# LEDAnzeige_Multiplexing.net
KiCad netlist of a schematic drawn in EAGLE
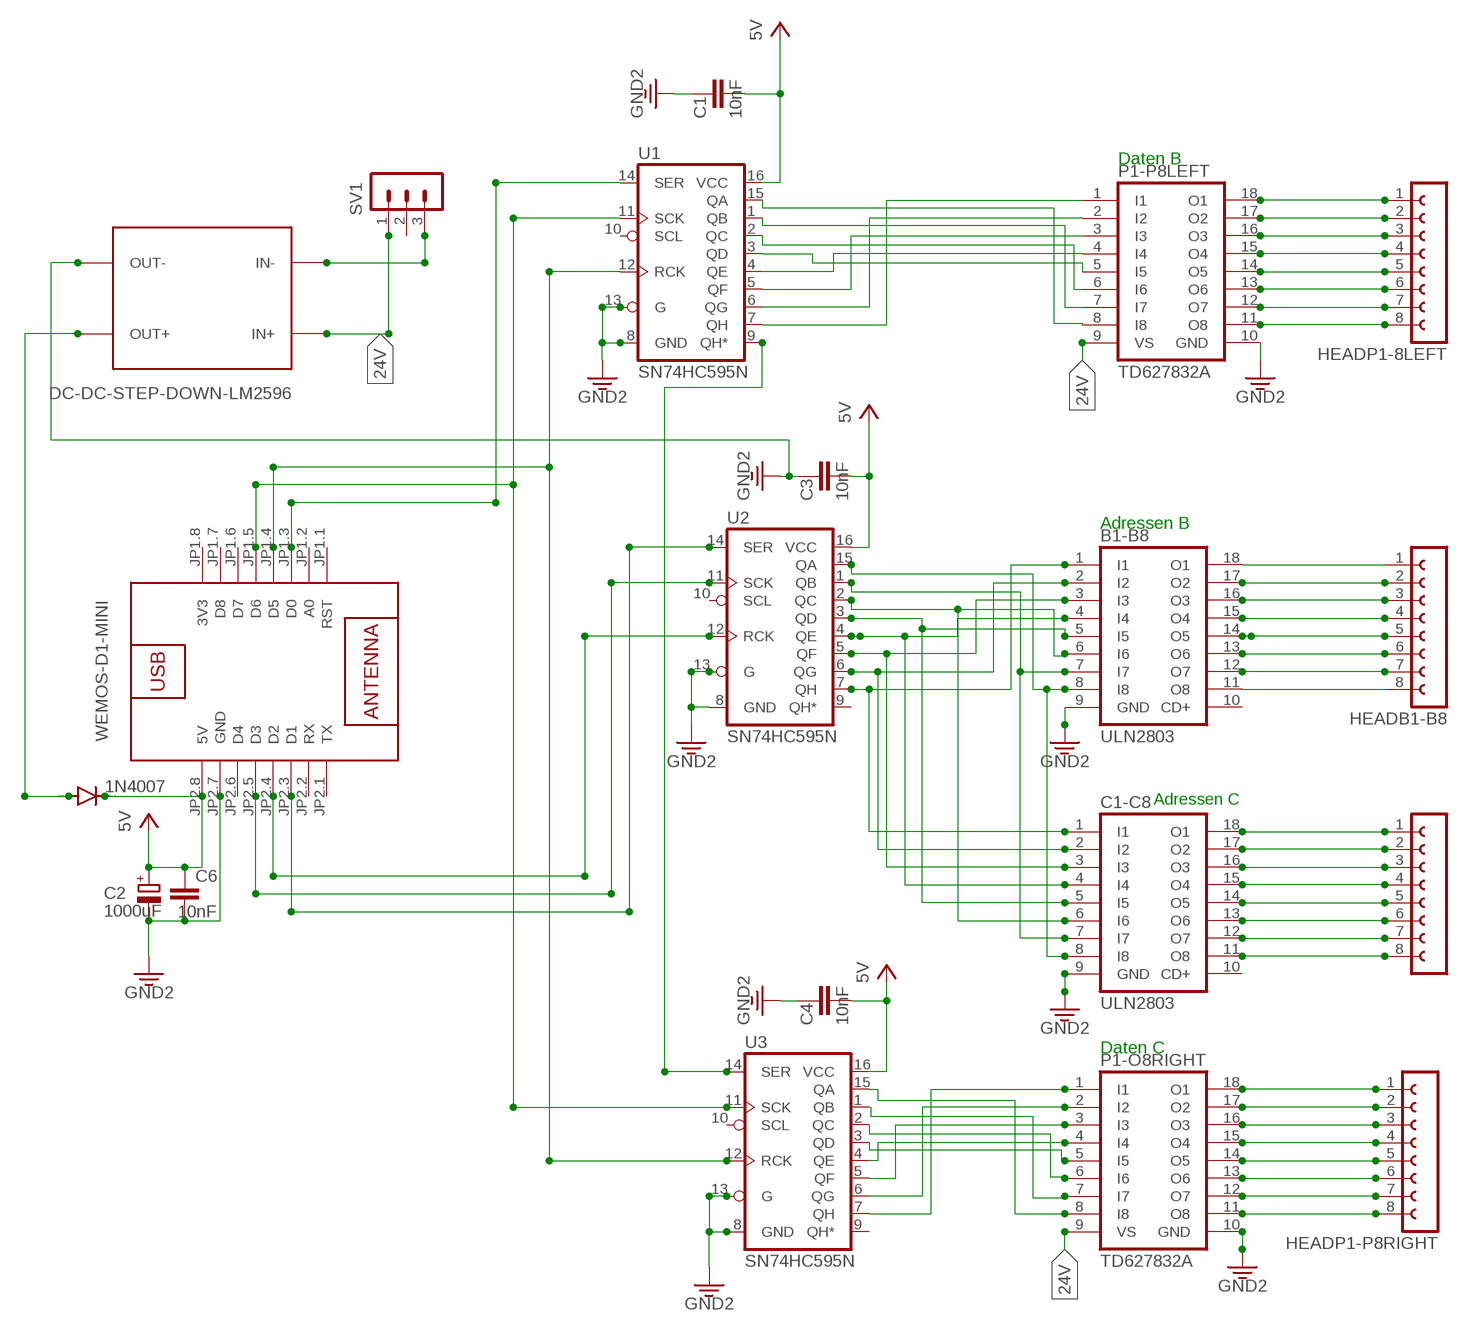
[diagram p0: schematic, sheet 1]

(export (version "E")
  (design (tool "Eeschema 10.0.6"))
  (components
    (comp (ref "1N4007")
      (value "DIODE-D-2.5")
      (footprint "eagle-import:D-2.5")
      (libsource (lib "eagle-import") (part "DIODE-D-2.5"))
    )
    (comp (ref "B1-B8")
      (value "ULN2803")
      (footprint "eagle-import:DIL18")
      (libsource (lib "eagle-import") (part "ULN2803A"))
    )
    (comp (ref "C1")
      (value "10nF")
      (footprint "eagle-import:C025-025X050")
      (libsource (lib "eagle-import") (part "C-EU025-025X050"))
    )
    (comp (ref "C1-C8")
      (value "ULN2803")
      (footprint "eagle-import:DIL18")
      (libsource (lib "eagle-import") (part "ULN2803A"))
    )
    (comp (ref "C2")
      (value "1000uF")
      (footprint "eagle-import:E5-10,5")
      (libsource (lib "eagle-import") (part "CPOL-EUE5-10.5"))
    )
    (comp (ref "C3")
      (value "10nF")
      (footprint "eagle-import:C025-025X050")
      (libsource (lib "eagle-import") (part "C-EU025-025X050"))
    )
    (comp (ref "C4")
      (value "10nF")
      (footprint "eagle-import:C025-025X050")
      (libsource (lib "eagle-import") (part "C-EU025-025X050"))
    )
    (comp (ref "C6")
      (value "10nF")
      (footprint "eagle-import:C025-025X050")
      (libsource (lib "eagle-import") (part "C-EU025-025X050"))
    )
    (comp (ref "HEADB1-B8")
      (value "FE08-1")
      (footprint "eagle-import:FE08")
      (libsource (lib "eagle-import") (part "FE08-1"))
    )
    (comp (ref "HEADC1-C8")
      (value "FE08-1")
      (footprint "eagle-import:FE08")
      (libsource (lib "eagle-import") (part "FE08-1"))
    )
    (comp (ref "HEADP1-8LEFT")
      (value "FE08-1")
      (footprint "eagle-import:FE08")
      (libsource (lib "eagle-import") (part "FE08-1"))
    )
    (comp (ref "HEADP1-P8RIGHT")
      (value "FE08-1")
      (footprint "eagle-import:FE08")
      (libsource (lib "eagle-import") (part "FE08-1"))
    )
    (comp (ref "P1-O8RIGHT")
      (value "TD627832A")
      (footprint "eagle-import:DIL18")
      (libsource (lib "eagle-import") (part "TD62783A2"))
    )
    (comp (ref "P1-P8LEFT")
      (value "TD627832A")
      (footprint "eagle-import:DIL18")
      (libsource (lib "eagle-import") (part "TD62783A2"))
    )
    (comp (ref "SV1")
      (value "MA03-1")
      (footprint "eagle-import:MA03-1")
      (libsource (lib "eagle-import") (part "MA03-1"))
    )
    (comp (ref "U$1")
      (value "WEMOS-D1-MINI")
      (footprint "eagle-import:WEMOS-D1-MINI")
      (libsource (lib "eagle-import") (part "WEMOS-D1-MINI"))
    )
    (comp (ref "U$2")
      (value "DC-DC-STEP-DOWN-LM2596")
      (footprint "eagle-import:DC-DC-STEP-DOWN-LM2596")
      (libsource (lib "eagle-import") (part "DC-DC-STEP-DOWN-LM2596"))
    )
    (comp (ref "U1")
      (value "SN74HC595N")
      (footprint "eagle-import:DIP16")
      (libsource (lib "eagle-import") (part "74595NHC"))
    )
    (comp (ref "U2")
      (value "SN74HC595N")
      (footprint "eagle-import:DIP16")
      (libsource (lib "eagle-import") (part "74595NHC"))
    )
    (comp (ref "U3")
      (value "SN74HC595N")
      (footprint "eagle-import:DIP16")
      (libsource (lib "eagle-import") (part "74595NHC"))
    )
  )
  (nets
    (net (code "1") (name "/3V3") (class "Default")
      (node (ref "U$1") (pin "JP1.8") (pinfunction "3V3_JP1.8") (pintype "power_in"))
    )
    (net (code "2") (name "5V") (class "Default")
      (node (ref "1N4007") (pin "C") (pinfunction "C_C") (pintype "passive"))
      (node (ref "C1") (pin "2") (pinfunction "2_2") (pintype "passive"))
      (node (ref "C2") (pin "+") (pinfunction "+_+") (pintype "passive"))
      (node (ref "C3") (pin "2") (pinfunction "2_2") (pintype "passive"))
      (node (ref "C4") (pin "2") (pinfunction "2_2") (pintype "passive"))
      (node (ref "C6") (pin "1") (pinfunction "1_1") (pintype "passive"))
      (node (ref "U$1") (pin "JP2.8") (pinfunction "5V_JP2.8") (pintype "power_in"))
      (node (ref "U1") (pin "16") (pinfunction "VCC_16") (pintype "power_in"))
      (node (ref "U2") (pin "16") (pinfunction "VCC_16") (pintype "power_in"))
      (node (ref "U3") (pin "16") (pinfunction "VCC_16") (pintype "power_in"))
    )
    (net (code "3") (name "24V") (class "Default")
      (node (ref "P1-O8RIGHT") (pin "9") (pinfunction "VS_9") (pintype "passive"))
      (node (ref "P1-P8LEFT") (pin "9") (pinfunction "VS_9") (pintype "passive"))
      (node (ref "SV1") (pin "1") (pinfunction "1_1") (pintype "passive"))
      (node (ref "U$2") (pin "IN+") (pinfunction "IN+_IN+") (pintype "bidirectional"))
    )
    (net (code "4") (name "GND2") (class "Default")
      (node (ref "B1-B8") (pin "9") (pinfunction "GND_9") (pintype "power_in"))
      (node (ref "C1") (pin "1") (pinfunction "1_1") (pintype "passive"))
      (node (ref "C1-C8") (pin "9") (pinfunction "GND_9") (pintype "power_in"))
      (node (ref "C2") (pin "-") (pinfunction "-_-") (pintype "passive"))
      (node (ref "C3") (pin "1") (pinfunction "1_1") (pintype "passive"))
      (node (ref "C4") (pin "1") (pinfunction "1_1") (pintype "passive"))
      (node (ref "C6") (pin "2") (pinfunction "2_2") (pintype "passive"))
      (node (ref "P1-O8RIGHT") (pin "10") (pinfunction "GND_10") (pintype "power_in"))
      (node (ref "P1-P8LEFT") (pin "10") (pinfunction "GND_10") (pintype "power_in"))
      (node (ref "U$1") (pin "JP2.7") (pinfunction "GND_JP2.7") (pintype "power_in"))
      (node (ref "U$2") (pin "OUT-") (pinfunction "OUT-_OUT-") (pintype "bidirectional"))
      (node (ref "U1") (pin "13") (pinfunction "G_13") (pintype "input"))
      (node (ref "U1") (pin "8") (pinfunction "GND_8") (pintype "power_in"))
      (node (ref "U2") (pin "13") (pinfunction "G_13") (pintype "input"))
      (node (ref "U2") (pin "8") (pinfunction "GND_8") (pintype "power_in"))
      (node (ref "U3") (pin "13") (pinfunction "G_13") (pintype "input"))
      (node (ref "U3") (pin "8") (pinfunction "GND_8") (pintype "power_in"))
    )
    (net (code "5") (name "Net-(1N4007-PadA)") (class "Default")
      (node (ref "1N4007") (pin "A") (pinfunction "A_A") (pintype "passive"))
      (node (ref "U$2") (pin "OUT+") (pinfunction "OUT+_OUT+") (pintype "bidirectional"))
    )
    (net (code "6") (name "Net-(B1-B8-I1)") (class "Default")
      (node (ref "B1-B8") (pin "1") (pinfunction "I1_1") (pintype "input"))
      (node (ref "C1-C8") (pin "1") (pinfunction "I1_1") (pintype "input"))
      (node (ref "U2") (pin "7") (pinfunction "QH_7") (pintype "tri_state"))
    )
    (net (code "7") (name "Net-(B1-B8-I2)") (class "Default")
      (node (ref "B1-B8") (pin "2") (pinfunction "I2_2") (pintype "input"))
      (node (ref "C1-C8") (pin "2") (pinfunction "I2_2") (pintype "input"))
      (node (ref "U2") (pin "6") (pinfunction "QG_6") (pintype "tri_state"))
    )
    (net (code "8") (name "Net-(B1-B8-I3)") (class "Default")
      (node (ref "B1-B8") (pin "3") (pinfunction "I3_3") (pintype "input"))
      (node (ref "C1-C8") (pin "3") (pinfunction "I3_3") (pintype "input"))
      (node (ref "U2") (pin "5") (pinfunction "QF_5") (pintype "tri_state"))
    )
    (net (code "9") (name "Net-(B1-B8-I4)") (class "Default")
      (node (ref "B1-B8") (pin "4") (pinfunction "I4_4") (pintype "input"))
      (node (ref "C1-C8") (pin "4") (pinfunction "I4_4") (pintype "input"))
      (node (ref "U2") (pin "4") (pinfunction "QE_4") (pintype "tri_state"))
    )
    (net (code "10") (name "Net-(B1-B8-I5)") (class "Default")
      (node (ref "B1-B8") (pin "5") (pinfunction "I5_5") (pintype "input"))
      (node (ref "C1-C8") (pin "5") (pinfunction "I5_5") (pintype "input"))
      (node (ref "U2") (pin "3") (pinfunction "QD_3") (pintype "tri_state"))
    )
    (net (code "11") (name "Net-(B1-B8-I6)") (class "Default")
      (node (ref "B1-B8") (pin "6") (pinfunction "I6_6") (pintype "input"))
      (node (ref "C1-C8") (pin "6") (pinfunction "I6_6") (pintype "input"))
      (node (ref "U2") (pin "2") (pinfunction "QC_2") (pintype "tri_state"))
    )
    (net (code "12") (name "Net-(B1-B8-I7)") (class "Default")
      (node (ref "B1-B8") (pin "7") (pinfunction "I7_7") (pintype "input"))
      (node (ref "C1-C8") (pin "7") (pinfunction "I7_7") (pintype "input"))
      (node (ref "U2") (pin "1") (pinfunction "QB_1") (pintype "tri_state"))
    )
    (net (code "13") (name "Net-(B1-B8-I8)") (class "Default")
      (node (ref "B1-B8") (pin "8") (pinfunction "I8_8") (pintype "input"))
      (node (ref "C1-C8") (pin "8") (pinfunction "I8_8") (pintype "input"))
      (node (ref "U2") (pin "15") (pinfunction "QA_15") (pintype "tri_state"))
    )
    (net (code "14") (name "Net-(B1-B8-O1)") (class "Default")
      (node (ref "B1-B8") (pin "18") (pinfunction "O1_18") (pintype "open_collector"))
      (node (ref "HEADB1-B8") (pin "1") (pinfunction "1_1") (pintype "passive"))
    )
    (net (code "15") (name "Net-(B1-B8-O2)") (class "Default")
      (node (ref "B1-B8") (pin "17") (pinfunction "O2_17") (pintype "open_collector"))
      (node (ref "HEADB1-B8") (pin "2") (pinfunction "2_2") (pintype "passive"))
    )
    (net (code "16") (name "Net-(B1-B8-O3)") (class "Default")
      (node (ref "B1-B8") (pin "16") (pinfunction "O3_16") (pintype "open_collector"))
      (node (ref "HEADB1-B8") (pin "3") (pinfunction "3_3") (pintype "passive"))
    )
    (net (code "17") (name "Net-(B1-B8-O4)") (class "Default")
      (node (ref "B1-B8") (pin "15") (pinfunction "O4_15") (pintype "open_collector"))
      (node (ref "HEADB1-B8") (pin "4") (pinfunction "4_4") (pintype "passive"))
    )
    (net (code "18") (name "Net-(B1-B8-O5)") (class "Default")
      (node (ref "B1-B8") (pin "14") (pinfunction "O5_14") (pintype "open_collector"))
      (node (ref "HEADB1-B8") (pin "5") (pinfunction "5_5") (pintype "passive"))
    )
    (net (code "19") (name "Net-(B1-B8-O6)") (class "Default")
      (node (ref "B1-B8") (pin "13") (pinfunction "O6_13") (pintype "open_collector"))
      (node (ref "HEADB1-B8") (pin "6") (pinfunction "6_6") (pintype "passive"))
    )
    (net (code "20") (name "Net-(B1-B8-O7)") (class "Default")
      (node (ref "B1-B8") (pin "12") (pinfunction "O7_12") (pintype "open_collector"))
      (node (ref "HEADB1-B8") (pin "7") (pinfunction "7_7") (pintype "passive"))
    )
    (net (code "21") (name "Net-(B1-B8-O8)") (class "Default")
      (node (ref "B1-B8") (pin "11") (pinfunction "O8_11") (pintype "open_collector"))
      (node (ref "HEADB1-B8") (pin "8") (pinfunction "8_8") (pintype "passive"))
    )
    (net (code "22") (name "Net-(C1-C8-O1)") (class "Default")
      (node (ref "C1-C8") (pin "18") (pinfunction "O1_18") (pintype "open_collector"))
      (node (ref "HEADC1-C8") (pin "1") (pinfunction "1_1") (pintype "passive"))
    )
    (net (code "23") (name "Net-(C1-C8-O2)") (class "Default")
      (node (ref "C1-C8") (pin "17") (pinfunction "O2_17") (pintype "open_collector"))
      (node (ref "HEADC1-C8") (pin "2") (pinfunction "2_2") (pintype "passive"))
    )
    (net (code "24") (name "Net-(C1-C8-O3)") (class "Default")
      (node (ref "C1-C8") (pin "16") (pinfunction "O3_16") (pintype "open_collector"))
      (node (ref "HEADC1-C8") (pin "3") (pinfunction "3_3") (pintype "passive"))
    )
    (net (code "25") (name "Net-(C1-C8-O4)") (class "Default")
      (node (ref "C1-C8") (pin "15") (pinfunction "O4_15") (pintype "open_collector"))
      (node (ref "HEADC1-C8") (pin "4") (pinfunction "4_4") (pintype "passive"))
    )
    (net (code "26") (name "Net-(C1-C8-O5)") (class "Default")
      (node (ref "C1-C8") (pin "14") (pinfunction "O5_14") (pintype "open_collector"))
      (node (ref "HEADC1-C8") (pin "5") (pinfunction "5_5") (pintype "passive"))
    )
    (net (code "27") (name "Net-(C1-C8-O6)") (class "Default")
      (node (ref "C1-C8") (pin "13") (pinfunction "O6_13") (pintype "open_collector"))
      (node (ref "HEADC1-C8") (pin "6") (pinfunction "6_6") (pintype "passive"))
    )
    (net (code "28") (name "Net-(C1-C8-O7)") (class "Default")
      (node (ref "C1-C8") (pin "12") (pinfunction "O7_12") (pintype "open_collector"))
      (node (ref "HEADC1-C8") (pin "7") (pinfunction "7_7") (pintype "passive"))
    )
    (net (code "29") (name "Net-(C1-C8-O8)") (class "Default")
      (node (ref "C1-C8") (pin "11") (pinfunction "O8_11") (pintype "open_collector"))
      (node (ref "HEADC1-C8") (pin "8") (pinfunction "8_8") (pintype "passive"))
    )
    (net (code "30") (name "Net-(P1-O8RIGHT-I1)") (class "Default")
      (node (ref "P1-O8RIGHT") (pin "1") (pinfunction "I1_1") (pintype "input"))
      (node (ref "U3") (pin "7") (pinfunction "QH_7") (pintype "tri_state"))
    )
    (net (code "31") (name "Net-(P1-O8RIGHT-I2)") (class "Default")
      (node (ref "P1-O8RIGHT") (pin "2") (pinfunction "I2_2") (pintype "input"))
      (node (ref "U3") (pin "6") (pinfunction "QG_6") (pintype "tri_state"))
    )
    (net (code "32") (name "Net-(P1-O8RIGHT-I3)") (class "Default")
      (node (ref "P1-O8RIGHT") (pin "3") (pinfunction "I3_3") (pintype "input"))
      (node (ref "U3") (pin "5") (pinfunction "QF_5") (pintype "tri_state"))
    )
    (net (code "33") (name "Net-(P1-O8RIGHT-I4)") (class "Default")
      (node (ref "P1-O8RIGHT") (pin "4") (pinfunction "I4_4") (pintype "input"))
      (node (ref "U3") (pin "4") (pinfunction "QE_4") (pintype "tri_state"))
    )
    (net (code "34") (name "Net-(P1-O8RIGHT-I5)") (class "Default")
      (node (ref "P1-O8RIGHT") (pin "5") (pinfunction "I5_5") (pintype "input"))
      (node (ref "U3") (pin "3") (pinfunction "QD_3") (pintype "tri_state"))
    )
    (net (code "35") (name "Net-(P1-O8RIGHT-I6)") (class "Default")
      (node (ref "P1-O8RIGHT") (pin "6") (pinfunction "I6_6") (pintype "input"))
      (node (ref "U3") (pin "2") (pinfunction "QC_2") (pintype "tri_state"))
    )
    (net (code "36") (name "Net-(P1-O8RIGHT-I7)") (class "Default")
      (node (ref "P1-O8RIGHT") (pin "7") (pinfunction "I7_7") (pintype "input"))
      (node (ref "U3") (pin "1") (pinfunction "QB_1") (pintype "tri_state"))
    )
    (net (code "37") (name "Net-(P1-O8RIGHT-I8)") (class "Default")
      (node (ref "P1-O8RIGHT") (pin "8") (pinfunction "I8_8") (pintype "input"))
      (node (ref "U3") (pin "15") (pinfunction "QA_15") (pintype "tri_state"))
    )
    (net (code "38") (name "Net-(P1-O8RIGHT-O1)") (class "Default")
      (node (ref "HEADP1-P8RIGHT") (pin "1") (pinfunction "1_1") (pintype "passive"))
      (node (ref "P1-O8RIGHT") (pin "18") (pinfunction "O1_18") (pintype "open_collector"))
    )
    (net (code "39") (name "Net-(P1-O8RIGHT-O2)") (class "Default")
      (node (ref "HEADP1-P8RIGHT") (pin "2") (pinfunction "2_2") (pintype "passive"))
      (node (ref "P1-O8RIGHT") (pin "17") (pinfunction "O2_17") (pintype "open_collector"))
    )
    (net (code "40") (name "Net-(P1-O8RIGHT-O3)") (class "Default")
      (node (ref "HEADP1-P8RIGHT") (pin "3") (pinfunction "3_3") (pintype "passive"))
      (node (ref "P1-O8RIGHT") (pin "16") (pinfunction "O3_16") (pintype "open_collector"))
    )
    (net (code "41") (name "Net-(P1-O8RIGHT-O4)") (class "Default")
      (node (ref "HEADP1-P8RIGHT") (pin "4") (pinfunction "4_4") (pintype "passive"))
      (node (ref "P1-O8RIGHT") (pin "15") (pinfunction "O4_15") (pintype "open_collector"))
    )
    (net (code "42") (name "Net-(P1-O8RIGHT-O5)") (class "Default")
      (node (ref "HEADP1-P8RIGHT") (pin "5") (pinfunction "5_5") (pintype "passive"))
      (node (ref "P1-O8RIGHT") (pin "14") (pinfunction "O5_14") (pintype "open_collector"))
    )
    (net (code "43") (name "Net-(P1-O8RIGHT-O6)") (class "Default")
      (node (ref "HEADP1-P8RIGHT") (pin "6") (pinfunction "6_6") (pintype "passive"))
      (node (ref "P1-O8RIGHT") (pin "13") (pinfunction "O6_13") (pintype "open_collector"))
    )
    (net (code "44") (name "Net-(P1-O8RIGHT-O7)") (class "Default")
      (node (ref "HEADP1-P8RIGHT") (pin "7") (pinfunction "7_7") (pintype "passive"))
      (node (ref "P1-O8RIGHT") (pin "12") (pinfunction "O7_12") (pintype "open_collector"))
    )
    (net (code "45") (name "Net-(P1-O8RIGHT-O8)") (class "Default")
      (node (ref "HEADP1-P8RIGHT") (pin "8") (pinfunction "8_8") (pintype "passive"))
      (node (ref "P1-O8RIGHT") (pin "11") (pinfunction "O8_11") (pintype "open_collector"))
    )
    (net (code "46") (name "Net-(P1-P8LEFT-I1)") (class "Default")
      (node (ref "P1-P8LEFT") (pin "1") (pinfunction "I1_1") (pintype "input"))
      (node (ref "U1") (pin "7") (pinfunction "QH_7") (pintype "tri_state"))
    )
    (net (code "47") (name "Net-(P1-P8LEFT-I2)") (class "Default")
      (node (ref "P1-P8LEFT") (pin "2") (pinfunction "I2_2") (pintype "input"))
      (node (ref "U1") (pin "6") (pinfunction "QG_6") (pintype "tri_state"))
    )
    (net (code "48") (name "Net-(P1-P8LEFT-I3)") (class "Default")
      (node (ref "P1-P8LEFT") (pin "3") (pinfunction "I3_3") (pintype "input"))
      (node (ref "U1") (pin "5") (pinfunction "QF_5") (pintype "tri_state"))
    )
    (net (code "49") (name "Net-(P1-P8LEFT-I4)") (class "Default")
      (node (ref "P1-P8LEFT") (pin "4") (pinfunction "I4_4") (pintype "input"))
      (node (ref "U1") (pin "4") (pinfunction "QE_4") (pintype "tri_state"))
    )
    (net (code "50") (name "Net-(P1-P8LEFT-I5)") (class "Default")
      (node (ref "P1-P8LEFT") (pin "5") (pinfunction "I5_5") (pintype "input"))
      (node (ref "U1") (pin "3") (pinfunction "QD_3") (pintype "tri_state"))
    )
    (net (code "51") (name "Net-(P1-P8LEFT-I6)") (class "Default")
      (node (ref "P1-P8LEFT") (pin "6") (pinfunction "I6_6") (pintype "input"))
      (node (ref "U1") (pin "2") (pinfunction "QC_2") (pintype "tri_state"))
    )
    (net (code "52") (name "Net-(P1-P8LEFT-I7)") (class "Default")
      (node (ref "P1-P8LEFT") (pin "7") (pinfunction "I7_7") (pintype "input"))
      (node (ref "U1") (pin "1") (pinfunction "QB_1") (pintype "tri_state"))
    )
    (net (code "53") (name "Net-(P1-P8LEFT-I8)") (class "Default")
      (node (ref "P1-P8LEFT") (pin "8") (pinfunction "I8_8") (pintype "input"))
      (node (ref "U1") (pin "15") (pinfunction "QA_15") (pintype "tri_state"))
    )
    (net (code "54") (name "Net-(P1-P8LEFT-O1)") (class "Default")
      (node (ref "HEADP1-8LEFT") (pin "1") (pinfunction "1_1") (pintype "passive"))
      (node (ref "P1-P8LEFT") (pin "18") (pinfunction "O1_18") (pintype "open_collector"))
    )
    (net (code "55") (name "Net-(P1-P8LEFT-O2)") (class "Default")
      (node (ref "HEADP1-8LEFT") (pin "2") (pinfunction "2_2") (pintype "passive"))
      (node (ref "P1-P8LEFT") (pin "17") (pinfunction "O2_17") (pintype "open_collector"))
    )
    (net (code "56") (name "Net-(P1-P8LEFT-O3)") (class "Default")
      (node (ref "HEADP1-8LEFT") (pin "3") (pinfunction "3_3") (pintype "passive"))
      (node (ref "P1-P8LEFT") (pin "16") (pinfunction "O3_16") (pintype "open_collector"))
    )
    (net (code "57") (name "Net-(P1-P8LEFT-O4)") (class "Default")
      (node (ref "HEADP1-8LEFT") (pin "4") (pinfunction "4_4") (pintype "passive"))
      (node (ref "P1-P8LEFT") (pin "15") (pinfunction "O4_15") (pintype "open_collector"))
    )
    (net (code "58") (name "Net-(P1-P8LEFT-O5)") (class "Default")
      (node (ref "HEADP1-8LEFT") (pin "5") (pinfunction "5_5") (pintype "passive"))
      (node (ref "P1-P8LEFT") (pin "14") (pinfunction "O5_14") (pintype "open_collector"))
    )
    (net (code "59") (name "Net-(P1-P8LEFT-O6)") (class "Default")
      (node (ref "HEADP1-8LEFT") (pin "6") (pinfunction "6_6") (pintype "passive"))
      (node (ref "P1-P8LEFT") (pin "13") (pinfunction "O6_13") (pintype "open_collector"))
    )
    (net (code "60") (name "Net-(P1-P8LEFT-O7)") (class "Default")
      (node (ref "HEADP1-8LEFT") (pin "7") (pinfunction "7_7") (pintype "passive"))
      (node (ref "P1-P8LEFT") (pin "12") (pinfunction "O7_12") (pintype "open_collector"))
    )
    (net (code "61") (name "Net-(P1-P8LEFT-O8)") (class "Default")
      (node (ref "HEADP1-8LEFT") (pin "8") (pinfunction "8_8") (pintype "passive"))
      (node (ref "P1-P8LEFT") (pin "11") (pinfunction "O8_11") (pintype "open_collector"))
    )
    (net (code "62") (name "Net-(SV1-Pad3)") (class "Default")
      (node (ref "SV1") (pin "3") (pinfunction "3_3") (pintype "passive"))
      (node (ref "U$2") (pin "IN-") (pinfunction "IN-_IN-") (pintype "bidirectional"))
    )
    (net (code "63") (name "Net-(U$1-D0)") (class "Default")
      (node (ref "U$1") (pin "JP1.3") (pinfunction "D0_JP1.3") (pintype "bidirectional"))
      (node (ref "U1") (pin "14") (pinfunction "SER_14") (pintype "input"))
    )
    (net (code "64") (name "Net-(U$1-D1)") (class "Default")
      (node (ref "U$1") (pin "JP2.3") (pinfunction "D1_JP2.3") (pintype "bidirectional"))
      (node (ref "U2") (pin "14") (pinfunction "SER_14") (pintype "input"))
    )
    (net (code "65") (name "Net-(U$1-D2)") (class "Default")
      (node (ref "U$1") (pin "JP2.4") (pinfunction "D2_JP2.4") (pintype "bidirectional"))
      (node (ref "U2") (pin "12") (pinfunction "RCK_12") (pintype "input"))
    )
    (net (code "66") (name "Net-(U$1-D3)") (class "Default")
      (node (ref "U$1") (pin "JP2.5") (pinfunction "D3_JP2.5") (pintype "bidirectional"))
      (node (ref "U2") (pin "11") (pinfunction "SCK_11") (pintype "input"))
    )
    (net (code "67") (name "Net-(U$1-D5)") (class "Default")
      (node (ref "U$1") (pin "JP1.4") (pinfunction "D5_JP1.4") (pintype "bidirectional"))
      (node (ref "U1") (pin "12") (pinfunction "RCK_12") (pintype "input"))
      (node (ref "U3") (pin "12") (pinfunction "RCK_12") (pintype "input"))
    )
    (net (code "68") (name "Net-(U$1-D6)") (class "Default")
      (node (ref "U$1") (pin "JP1.5") (pinfunction "D6_JP1.5") (pintype "bidirectional"))
      (node (ref "U1") (pin "11") (pinfunction "SCK_11") (pintype "input"))
      (node (ref "U3") (pin "11") (pinfunction "SCK_11") (pintype "input"))
    )
    (net (code "69") (name "Net-(U1-QH*)") (class "Default")
      (node (ref "U1") (pin "9") (pinfunction "QH*_9") (pintype "tri_state"))
      (node (ref "U3") (pin "14") (pinfunction "SER_14") (pintype "input"))
    )
    (net (code "70") (name "unconnected-(B1-B8-CD+-Pad10)") (class "Default")
      (node (ref "B1-B8") (pin "10") (pinfunction "CD+_10") (pintype "passive"))
    )
    (net (code "71") (name "unconnected-(C1-C8-CD+-Pad10)") (class "Default")
      (node (ref "C1-C8") (pin "10") (pinfunction "CD+_10") (pintype "passive"))
    )
    (net (code "72") (name "unconnected-(SV1-Pad2)") (class "Default")
      (node (ref "SV1") (pin "2") (pinfunction "2_2") (pintype "passive"))
    )
    (net (code "73") (name "unconnected-(U$1-A0-PadJP1.2)") (class "Default")
      (node (ref "U$1") (pin "JP1.2") (pinfunction "A0_JP1.2") (pintype "bidirectional"))
    )
    (net (code "74") (name "unconnected-(U$1-D4-PadJP2.6)") (class "Default")
      (node (ref "U$1") (pin "JP2.6") (pinfunction "D4_JP2.6") (pintype "bidirectional"))
    )
    (net (code "75") (name "unconnected-(U$1-D7-PadJP1.6)") (class "Default")
      (node (ref "U$1") (pin "JP1.6") (pinfunction "D7_JP1.6") (pintype "bidirectional"))
    )
    (net (code "76") (name "unconnected-(U$1-D8-PadJP1.7)") (class "Default")
      (node (ref "U$1") (pin "JP1.7") (pinfunction "D8_JP1.7") (pintype "bidirectional"))
    )
    (net (code "77") (name "unconnected-(U$1-RST-PadJP1.1)") (class "Default")
      (node (ref "U$1") (pin "JP1.1") (pinfunction "RST_JP1.1") (pintype "bidirectional"))
    )
    (net (code "78") (name "unconnected-(U$1-RX-PadJP2.2)") (class "Default")
      (node (ref "U$1") (pin "JP2.2") (pinfunction "RX_JP2.2") (pintype "bidirectional"))
    )
    (net (code "79") (name "unconnected-(U$1-TX-PadJP2.1)") (class "Default")
      (node (ref "U$1") (pin "JP2.1") (pinfunction "TX_JP2.1") (pintype "bidirectional"))
    )
    (net (code "80") (name "unconnected-(U1-SCL-Pad10)") (class "Default")
      (node (ref "U1") (pin "10") (pinfunction "SCL_10") (pintype "input"))
    )
    (net (code "81") (name "unconnected-(U2-QH*-Pad9)") (class "Default")
      (node (ref "U2") (pin "9") (pinfunction "QH*_9") (pintype "tri_state"))
    )
    (net (code "82") (name "unconnected-(U2-SCL-Pad10)") (class "Default")
      (node (ref "U2") (pin "10") (pinfunction "SCL_10") (pintype "input"))
    )
    (net (code "83") (name "unconnected-(U3-QH*-Pad9)") (class "Default")
      (node (ref "U3") (pin "9") (pinfunction "QH*_9") (pintype "tri_state"))
    )
    (net (code "84") (name "unconnected-(U3-SCL-Pad10)") (class "Default")
      (node (ref "U3") (pin "10") (pinfunction "SCL_10") (pintype "input"))
    )
  )
)
